# CCR3.net
KiCad netlist of a schematic drawn in EAGLE
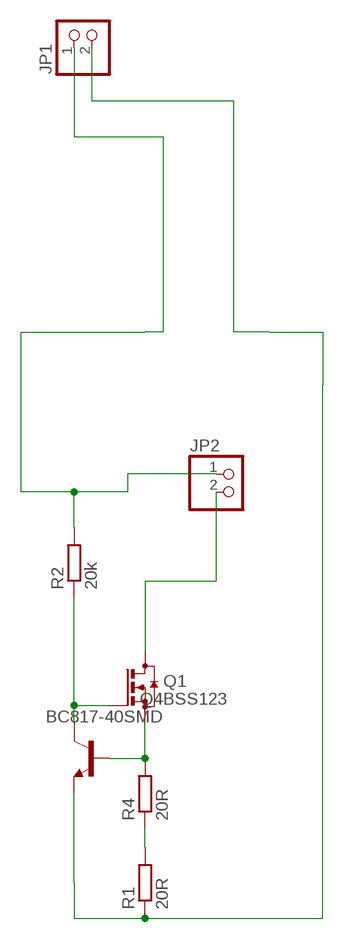
[diagram p0: schematic, sheet 1]

(export (version "E")
  (design (tool "Eeschema 10.0.6"))
  (components
    (comp (ref "JP1")
      (value "PINHD-1X2")
      (footprint "eagle-import:1X02")
      (libsource (lib "eagle-import") (part "PINHD-1X2"))
    )
    (comp (ref "JP2")
      (value "PINHD-1X2")
      (footprint "eagle-import:1X02")
      (libsource (lib "eagle-import") (part "PINHD-1X2"))
    )
    (comp (ref "Q1")
      (value "BSS123")
      (footprint "eagle-import:SOT23")
      (libsource (lib "eagle-import") (part "BSS123"))
    )
    (comp (ref "Q4")
      (value "BC817-40SMD")
      (footprint "eagle-import:SOT23-BEC")
      (libsource (lib "eagle-import") (part "BC817SMD-40"))
    )
    (comp (ref "R1")
      (value "20R")
      (footprint "eagle-import:R1206")
      (libsource (lib "eagle-import") (part "R-EU_R1206"))
    )
    (comp (ref "R2")
      (value "20k")
      (footprint "eagle-import:R1206")
      (libsource (lib "eagle-import") (part "R-EU_R1206"))
    )
    (comp (ref "R4")
      (value "20R")
      (footprint "eagle-import:R1206")
      (libsource (lib "eagle-import") (part "R-EU_R1206"))
    )
  )
  (nets
    (net (code "1") (name "Net-(JP1-Pad1)") (class "Default")
      (node (ref "JP1") (pin "1") (pinfunction "1_1") (pintype "passive"))
      (node (ref "JP2") (pin "1") (pinfunction "1_1") (pintype "passive"))
      (node (ref "R2") (pin "2") (pinfunction "2_2") (pintype "passive"))
    )
    (net (code "2") (name "Net-(JP1-Pad2)") (class "Default")
      (node (ref "JP1") (pin "2") (pinfunction "2_2") (pintype "passive"))
      (node (ref "Q4") (pin "E") (pinfunction "E_E") (pintype "passive"))
      (node (ref "R1") (pin "1") (pinfunction "1_1") (pintype "passive"))
    )
    (net (code "3") (name "Net-(Q1-D)") (class "Default")
      (node (ref "JP2") (pin "2") (pinfunction "2_2") (pintype "passive"))
      (node (ref "Q1") (pin "3") (pinfunction "D_3") (pintype "passive"))
    )
    (net (code "4") (name "Net-(Q1-G)") (class "Default")
      (node (ref "Q1") (pin "1") (pinfunction "G_1") (pintype "passive"))
      (node (ref "Q4") (pin "C") (pinfunction "C_C") (pintype "passive"))
      (node (ref "R2") (pin "1") (pinfunction "1_1") (pintype "passive"))
    )
    (net (code "5") (name "Net-(Q1-S)") (class "Default")
      (node (ref "Q1") (pin "2") (pinfunction "S_2") (pintype "passive"))
      (node (ref "Q4") (pin "B") (pinfunction "B_B") (pintype "passive"))
      (node (ref "R4") (pin "2") (pinfunction "2_2") (pintype "passive"))
    )
    (net (code "6") (name "Net-(R1-Pad2)") (class "Default")
      (node (ref "R1") (pin "2") (pinfunction "2_2") (pintype "passive"))
      (node (ref "R4") (pin "1") (pinfunction "1_1") (pintype "passive"))
    )
  )
)
